# Sheet2.net
KiCad netlist of a schematic drawn in Altium Designer
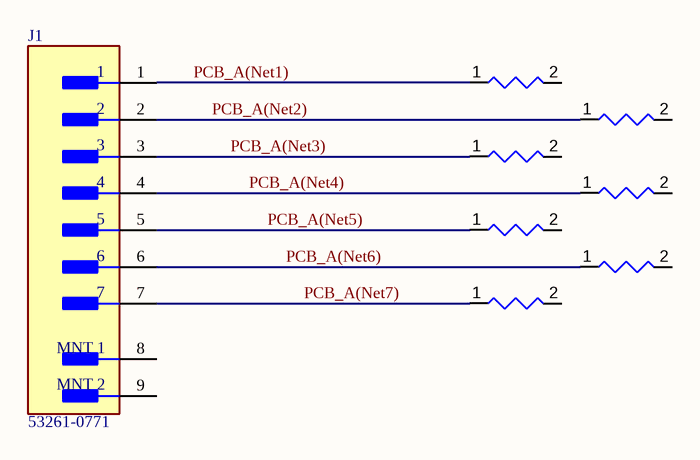
[diagram p0: Sheet2.SchDoc]

(export (version "E")
  (design (tool "Eeschema 10.0.6"))
  (components
    (comp (ref "J1")
      (value "53261-0771")
      (footprint "PCB2:FP-53261-0771-MFG")
      (fields (field (name "MANUFACTURER") "Molex"))
      (libsource (lib "Harness_Demo_PCB_A") (part "CMP-002-00075-1"))
    )
    (comp (ref "R1")
      (value "Resistor 10k +/-1% 1206 250 mW")
      (footprint "RESC3216X60X45ML15T20")
      (description "Chip Resistor, 10 KOhm, +/- 1%, 0.25 W, -55 to 155 degC, 1206 (3216 Metric)")
      (fields (field (name "TOLERANCE") "1%") (field (name "POWER") "250mW"))
      (libsource (lib "SCH") (part "RES-2"))
    )
    (comp (ref "R2")
      (value "Resistor 10k +/-1% 1206 250 mW")
      (footprint "RESC3216X60X45ML15T20")
      (description "Chip Resistor, 10 KOhm, +/- 1%, 0.25 W, -55 to 155 degC, 1206 (3216 Metric)")
      (fields (field (name "TOLERANCE") "1%") (field (name "POWER") "250mW"))
      (libsource (lib "SCH") (part "RES-2"))
    )
    (comp (ref "R3")
      (value "Resistor 10k +/-1% 1206 250 mW")
      (footprint "RESC3216X60X45ML15T20")
      (description "Chip Resistor, 10 KOhm, +/- 1%, 0.25 W, -55 to 155 degC, 1206 (3216 Metric)")
      (fields (field (name "TOLERANCE") "1%") (field (name "POWER") "250mW"))
      (libsource (lib "SCH") (part "RES-2"))
    )
    (comp (ref "R4")
      (value "Resistor 10k +/-1% 1206 250 mW")
      (footprint "RESC3216X60X45ML15T20")
      (description "Chip Resistor, 10 KOhm, +/- 1%, 0.25 W, -55 to 155 degC, 1206 (3216 Metric)")
      (fields (field (name "TOLERANCE") "1%") (field (name "POWER") "250mW"))
      (libsource (lib "SCH") (part "RES-2"))
    )
    (comp (ref "R5")
      (value "Resistor 10k +/-1% 1206 250 mW")
      (footprint "RESC3216X60X45ML15T20")
      (description "Chip Resistor, 10 KOhm, +/- 1%, 0.25 W, -55 to 155 degC, 1206 (3216 Metric)")
      (fields (field (name "TOLERANCE") "1%") (field (name "POWER") "250mW"))
      (libsource (lib "SCH") (part "RES-2"))
    )
    (comp (ref "R6")
      (value "Resistor 10k +/-1% 1206 250 mW")
      (footprint "RESC3216X60X45ML15T20")
      (description "Chip Resistor, 10 KOhm, +/- 1%, 0.25 W, -55 to 155 degC, 1206 (3216 Metric)")
      (fields (field (name "TOLERANCE") "1%") (field (name "POWER") "250mW"))
      (libsource (lib "SCH") (part "RES-2"))
    )
    (comp (ref "R7")
      (value "Resistor 10k +/-1% 1206 250 mW")
      (footprint "RESC3216X60X45ML15T20")
      (description "Chip Resistor, 10 KOhm, +/- 1%, 0.25 W, -55 to 155 degC, 1206 (3216 Metric)")
      (fields (field (name "TOLERANCE") "1%") (field (name "POWER") "250mW"))
      (libsource (lib "SCH") (part "RES-2"))
    )
  )
  (nets
    (net (code "1") (name "/PCB_A(Net1)") (class "Default")
      (node (ref "J1") (pin "1") (pinfunction "1_1") (pintype "passive"))
      (node (ref "R1") (pin "1") (pinfunction "1_1") (pintype "passive"))
    )
    (net (code "2") (name "/PCB_A(Net2)") (class "Default")
      (node (ref "J1") (pin "2") (pinfunction "2_2") (pintype "passive"))
      (node (ref "R2") (pin "1") (pinfunction "1_1") (pintype "passive"))
    )
    (net (code "3") (name "/PCB_A(Net3)") (class "Default")
      (node (ref "J1") (pin "3") (pinfunction "3_3") (pintype "passive"))
      (node (ref "R3") (pin "1") (pinfunction "1_1") (pintype "passive"))
    )
    (net (code "4") (name "/PCB_A(Net4)") (class "Default")
      (node (ref "J1") (pin "4") (pinfunction "4_4") (pintype "passive"))
      (node (ref "R4") (pin "1") (pinfunction "1_1") (pintype "passive"))
    )
    (net (code "5") (name "/PCB_A(Net5)") (class "Default")
      (node (ref "J1") (pin "5") (pinfunction "5_5") (pintype "passive"))
      (node (ref "R5") (pin "1") (pinfunction "1_1") (pintype "passive"))
    )
    (net (code "6") (name "/PCB_A(Net6)") (class "Default")
      (node (ref "J1") (pin "6") (pinfunction "6_6") (pintype "passive"))
      (node (ref "R6") (pin "1") (pinfunction "1_1") (pintype "passive"))
    )
    (net (code "7") (name "/PCB_A(Net7)") (class "Default")
      (node (ref "J1") (pin "7") (pinfunction "7_7") (pintype "passive"))
      (node (ref "R7") (pin "1") (pinfunction "1_1") (pintype "passive"))
    )
    (net (code "8") (name "unconnected-(J1-MNT_1-Pad8)") (class "Default")
      (node (ref "J1") (pin "8") (pinfunction "MNT_1_8") (pintype "passive"))
    )
    (net (code "9") (name "unconnected-(J1-MNT_2-Pad9)") (class "Default")
      (node (ref "J1") (pin "9") (pinfunction "MNT_2_9") (pintype "passive"))
    )
    (net (code "10") (name "unconnected-(R1-Pad2)") (class "Default")
      (node (ref "R1") (pin "2") (pinfunction "2_2") (pintype "passive"))
    )
    (net (code "11") (name "unconnected-(R2-Pad2)") (class "Default")
      (node (ref "R2") (pin "2") (pinfunction "2_2") (pintype "passive"))
    )
    (net (code "12") (name "unconnected-(R3-Pad2)") (class "Default")
      (node (ref "R3") (pin "2") (pinfunction "2_2") (pintype "passive"))
    )
    (net (code "13") (name "unconnected-(R4-Pad2)") (class "Default")
      (node (ref "R4") (pin "2") (pinfunction "2_2") (pintype "passive"))
    )
    (net (code "14") (name "unconnected-(R5-Pad2)") (class "Default")
      (node (ref "R5") (pin "2") (pinfunction "2_2") (pintype "passive"))
    )
    (net (code "15") (name "unconnected-(R6-Pad2)") (class "Default")
      (node (ref "R6") (pin "2") (pinfunction "2_2") (pintype "passive"))
    )
    (net (code "16") (name "unconnected-(R7-Pad2)") (class "Default")
      (node (ref "R7") (pin "2") (pinfunction "2_2") (pintype "passive"))
    )
  )
)
